# shieldplank.net
KiCad netlist of a schematic drawn in EAGLE
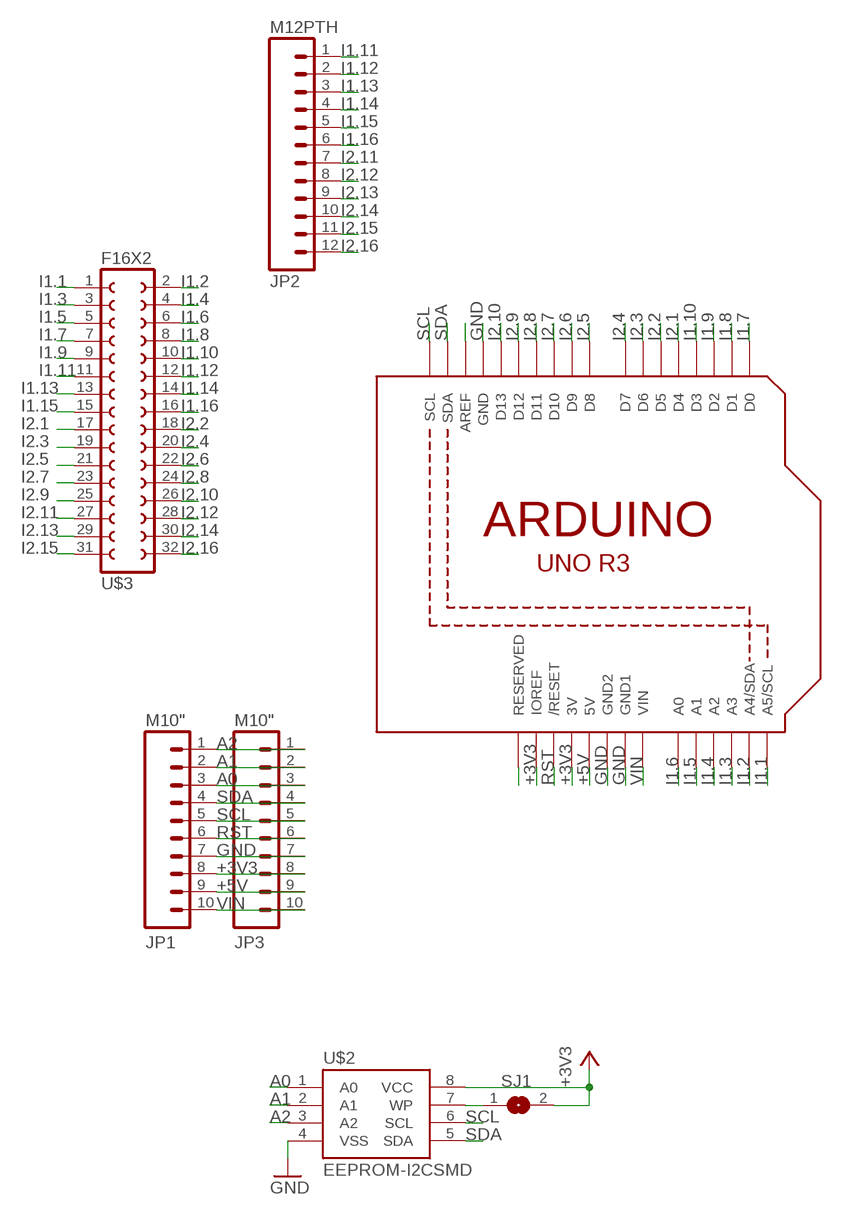
[diagram p0: schematic, sheet 1]

(export (version "E")
  (design (tool "Eeschema 10.0.6"))
  (components
    (comp (ref "JP1")
      (value "M10\"")
      (footprint "eagle-import:1X10")
      (libsource (lib "eagle-import") (part "M10{dblquote}"))
    )
    (comp (ref "JP2")
      (value "M12PTH")
      (footprint "eagle-import:1X12")
      (libsource (lib "eagle-import") (part "M12PTH"))
    )
    (comp (ref "JP3")
      (value "M10\"")
      (footprint "eagle-import:1X10")
      (libsource (lib "eagle-import") (part "M10{dblquote}"))
    )
    (comp (ref "SJ1") (value "SJ") (footprint "eagle-import:SJ") (libsource (lib "eagle-import") (part "SJ")))
    (comp (ref "U$2")
      (value "EEPROM-I2CSMD")
      (footprint "eagle-import:SO08")
      (libsource (lib "eagle-import") (part "EEPROM-I2CSMD"))
    )
    (comp (ref "U$3")
      (value "F16X2")
      (footprint "eagle-import:FE16-2")
      (libsource (lib "eagle-import") (part "F16X2"))
    )
    (comp (ref "U1")
      (value "ARDUINOR3-BPLACE")
      (footprint "eagle-import:ARDUINOR3-BPLACE")
      (libsource (lib "eagle-import") (part "ARDUINOR3-BPLACE"))
    )
  )
  (nets
    (net (code "1") (name "+3V3") (class "Default")
      (node (ref "JP1") (pin "8") (pinfunction "8_8") (pintype "passive"))
      (node (ref "JP3") (pin "8") (pinfunction "8_8") (pintype "passive"))
      (node (ref "SJ1") (pin "2") (pinfunction "2_2") (pintype "passive"))
      (node (ref "U$2") (pin "8") (pinfunction "VCC_8") (pintype "power_in"))
      (node (ref "U1") (pin "3V") (pinfunction "3V_3V") (pintype "power_in"))
      (node (ref "U1") (pin "IOREF") (pinfunction "IOREF_IOREF") (pintype "output"))
    )
    (net (code "2") (name "/+5V") (class "Default")
      (node (ref "JP1") (pin "9") (pinfunction "9_9") (pintype "passive"))
      (node (ref "JP3") (pin "9") (pinfunction "9_9") (pintype "passive"))
      (node (ref "U1") (pin "5V") (pinfunction "5V_5V") (pintype "power_in"))
    )
    (net (code "3") (name "/A0") (class "Default")
      (node (ref "JP1") (pin "3") (pinfunction "3_3") (pintype "passive"))
      (node (ref "JP3") (pin "3") (pinfunction "3_3") (pintype "passive"))
      (node (ref "U$2") (pin "1") (pinfunction "A0_1") (pintype "bidirectional"))
    )
    (net (code "4") (name "/A1") (class "Default")
      (node (ref "JP1") (pin "2") (pinfunction "2_2") (pintype "passive"))
      (node (ref "JP3") (pin "2") (pinfunction "2_2") (pintype "passive"))
      (node (ref "U$2") (pin "2") (pinfunction "A1_2") (pintype "bidirectional"))
    )
    (net (code "5") (name "/A2") (class "Default")
      (node (ref "JP1") (pin "1") (pinfunction "1_1") (pintype "passive"))
      (node (ref "JP3") (pin "1") (pinfunction "1_1") (pintype "passive"))
      (node (ref "U$2") (pin "3") (pinfunction "A2_3") (pintype "bidirectional"))
    )
    (net (code "6") (name "/I1.1") (class "Default")
      (node (ref "U$3") (pin "1") (pinfunction "1_1") (pintype "passive"))
      (node (ref "U1") (pin "A5") (pinfunction "A5/SCL_A5") (pintype "bidirectional"))
    )
    (net (code "7") (name "/I1.2") (class "Default")
      (node (ref "U$3") (pin "2") (pinfunction "2_2") (pintype "passive"))
      (node (ref "U1") (pin "A4") (pinfunction "A4/SDA_A4") (pintype "bidirectional"))
    )
    (net (code "8") (name "/I1.3") (class "Default")
      (node (ref "U$3") (pin "3") (pinfunction "3_3") (pintype "passive"))
      (node (ref "U1") (pin "A3") (pinfunction "A3_A3") (pintype "bidirectional"))
    )
    (net (code "9") (name "/I1.4") (class "Default")
      (node (ref "U$3") (pin "4") (pinfunction "4_4") (pintype "passive"))
      (node (ref "U1") (pin "A2") (pinfunction "A2_A2") (pintype "bidirectional"))
    )
    (net (code "10") (name "/I1.5") (class "Default")
      (node (ref "U$3") (pin "5") (pinfunction "5_5") (pintype "passive"))
      (node (ref "U1") (pin "A1") (pinfunction "A1_A1") (pintype "bidirectional"))
    )
    (net (code "11") (name "/I1.6") (class "Default")
      (node (ref "U$3") (pin "6") (pinfunction "6_6") (pintype "passive"))
      (node (ref "U1") (pin "A0") (pinfunction "A0_A0") (pintype "bidirectional"))
    )
    (net (code "12") (name "/I1.7") (class "Default")
      (node (ref "U$3") (pin "7") (pinfunction "7_7") (pintype "passive"))
      (node (ref "U1") (pin "D0") (pinfunction "D0_D0") (pintype "bidirectional"))
    )
    (net (code "13") (name "/I1.8") (class "Default")
      (node (ref "U$3") (pin "8") (pinfunction "8_8") (pintype "passive"))
      (node (ref "U1") (pin "D1") (pinfunction "D1_D1") (pintype "bidirectional"))
    )
    (net (code "14") (name "/I1.9") (class "Default")
      (node (ref "U$3") (pin "9") (pinfunction "9_9") (pintype "passive"))
      (node (ref "U1") (pin "D2") (pinfunction "D2_D2") (pintype "bidirectional"))
    )
    (net (code "15") (name "/I1.10") (class "Default")
      (node (ref "U$3") (pin "10") (pinfunction "10_10") (pintype "passive"))
      (node (ref "U1") (pin "D3") (pinfunction "D3_D3") (pintype "bidirectional"))
    )
    (net (code "16") (name "/I1.11") (class "Default")
      (node (ref "JP2") (pin "1") (pinfunction "1_1") (pintype "passive"))
      (node (ref "U$3") (pin "11") (pinfunction "11_11") (pintype "passive"))
    )
    (net (code "17") (name "/I1.12") (class "Default")
      (node (ref "JP2") (pin "2") (pinfunction "2_2") (pintype "passive"))
      (node (ref "U$3") (pin "12") (pinfunction "12_12") (pintype "passive"))
    )
    (net (code "18") (name "/I1.13") (class "Default")
      (node (ref "JP2") (pin "3") (pinfunction "3_3") (pintype "passive"))
      (node (ref "U$3") (pin "13") (pinfunction "13_13") (pintype "passive"))
    )
    (net (code "19") (name "/I1.14") (class "Default")
      (node (ref "JP2") (pin "4") (pinfunction "4_4") (pintype "passive"))
      (node (ref "U$3") (pin "14") (pinfunction "14_14") (pintype "passive"))
    )
    (net (code "20") (name "/I1.15") (class "Default")
      (node (ref "JP2") (pin "5") (pinfunction "5_5") (pintype "passive"))
      (node (ref "U$3") (pin "15") (pinfunction "15_15") (pintype "passive"))
    )
    (net (code "21") (name "/I1.16") (class "Default")
      (node (ref "JP2") (pin "6") (pinfunction "6_6") (pintype "passive"))
      (node (ref "U$3") (pin "16") (pinfunction "16_16") (pintype "passive"))
    )
    (net (code "22") (name "/I2.1") (class "Default")
      (node (ref "U$3") (pin "17") (pinfunction "17_17") (pintype "passive"))
      (node (ref "U1") (pin "D4") (pinfunction "D4_D4") (pintype "bidirectional"))
    )
    (net (code "23") (name "/I2.2") (class "Default")
      (node (ref "U$3") (pin "18") (pinfunction "18_18") (pintype "passive"))
      (node (ref "U1") (pin "D5") (pinfunction "D5_D5") (pintype "bidirectional"))
    )
    (net (code "24") (name "/I2.3") (class "Default")
      (node (ref "U$3") (pin "19") (pinfunction "19_19") (pintype "passive"))
      (node (ref "U1") (pin "D6") (pinfunction "D6_D6") (pintype "bidirectional"))
    )
    (net (code "25") (name "/I2.4") (class "Default")
      (node (ref "U$3") (pin "20") (pinfunction "20_20") (pintype "passive"))
      (node (ref "U1") (pin "D7") (pinfunction "D7_D7") (pintype "bidirectional"))
    )
    (net (code "26") (name "/I2.5") (class "Default")
      (node (ref "U$3") (pin "21") (pinfunction "21_21") (pintype "passive"))
      (node (ref "U1") (pin "D8") (pinfunction "D8_D8") (pintype "bidirectional"))
    )
    (net (code "27") (name "/I2.6") (class "Default")
      (node (ref "U$3") (pin "22") (pinfunction "22_22") (pintype "passive"))
      (node (ref "U1") (pin "D9") (pinfunction "D9_D9") (pintype "bidirectional"))
    )
    (net (code "28") (name "/I2.7") (class "Default")
      (node (ref "U$3") (pin "23") (pinfunction "23_23") (pintype "passive"))
      (node (ref "U1") (pin "D10") (pinfunction "D10_D10") (pintype "bidirectional"))
    )
    (net (code "29") (name "/I2.8") (class "Default")
      (node (ref "U$3") (pin "24") (pinfunction "24_24") (pintype "passive"))
      (node (ref "U1") (pin "D11") (pinfunction "D11_D11") (pintype "bidirectional"))
    )
    (net (code "30") (name "/I2.9") (class "Default")
      (node (ref "U$3") (pin "25") (pinfunction "25_25") (pintype "passive"))
      (node (ref "U1") (pin "D12") (pinfunction "D12_D12") (pintype "bidirectional"))
    )
    (net (code "31") (name "/I2.10") (class "Default")
      (node (ref "U$3") (pin "26") (pinfunction "26_26") (pintype "passive"))
      (node (ref "U1") (pin "D13") (pinfunction "D13_D13") (pintype "bidirectional"))
    )
    (net (code "32") (name "/I2.11") (class "Default")
      (node (ref "JP2") (pin "7") (pinfunction "7_7") (pintype "passive"))
      (node (ref "U$3") (pin "27") (pinfunction "27_27") (pintype "passive"))
    )
    (net (code "33") (name "/I2.12") (class "Default")
      (node (ref "JP2") (pin "8") (pinfunction "8_8") (pintype "passive"))
      (node (ref "U$3") (pin "28") (pinfunction "28_28") (pintype "passive"))
    )
    (net (code "34") (name "/I2.13") (class "Default")
      (node (ref "JP2") (pin "9") (pinfunction "9_9") (pintype "passive"))
      (node (ref "U$3") (pin "29") (pinfunction "29_29") (pintype "passive"))
    )
    (net (code "35") (name "/I2.14") (class "Default")
      (node (ref "JP2") (pin "10") (pinfunction "10_10") (pintype "passive"))
      (node (ref "U$3") (pin "30") (pinfunction "30_30") (pintype "passive"))
    )
    (net (code "36") (name "/I2.15") (class "Default")
      (node (ref "JP2") (pin "11") (pinfunction "11_11") (pintype "passive"))
      (node (ref "U$3") (pin "31") (pinfunction "31_31") (pintype "passive"))
    )
    (net (code "37") (name "/I2.16") (class "Default")
      (node (ref "JP2") (pin "12") (pinfunction "12_12") (pintype "passive"))
      (node (ref "U$3") (pin "32") (pinfunction "32_32") (pintype "passive"))
    )
    (net (code "38") (name "/RST") (class "Default")
      (node (ref "JP1") (pin "6") (pinfunction "6_6") (pintype "passive"))
      (node (ref "JP3") (pin "6") (pinfunction "6_6") (pintype "passive"))
      (node (ref "U1") (pin "RESET") (pinfunction "/RESET_RESET") (pintype "bidirectional"))
    )
    (net (code "39") (name "/SCL") (class "Default")
      (node (ref "JP1") (pin "5") (pinfunction "5_5") (pintype "passive"))
      (node (ref "JP3") (pin "5") (pinfunction "5_5") (pintype "passive"))
      (node (ref "U$2") (pin "6") (pinfunction "SCL_6") (pintype "bidirectional"))
      (node (ref "U1") (pin "SCL") (pinfunction "SCL_SCL") (pintype "bidirectional"))
    )
    (net (code "40") (name "/SDA") (class "Default")
      (node (ref "JP1") (pin "4") (pinfunction "4_4") (pintype "passive"))
      (node (ref "JP3") (pin "4") (pinfunction "4_4") (pintype "passive"))
      (node (ref "U$2") (pin "5") (pinfunction "SDA_5") (pintype "bidirectional"))
      (node (ref "U1") (pin "SDA") (pinfunction "SDA_SDA") (pintype "bidirectional"))
    )
    (net (code "41") (name "/VIN") (class "Default")
      (node (ref "JP1") (pin "10") (pinfunction "10_10") (pintype "passive"))
      (node (ref "JP3") (pin "10") (pinfunction "10_10") (pintype "passive"))
      (node (ref "U1") (pin "VIN") (pinfunction "VIN_VIN") (pintype "power_in"))
    )
    (net (code "42") (name "GND") (class "Default")
      (node (ref "JP1") (pin "7") (pinfunction "7_7") (pintype "passive"))
      (node (ref "JP3") (pin "7") (pinfunction "7_7") (pintype "passive"))
      (node (ref "U$2") (pin "4") (pinfunction "VSS_4") (pintype "power_in"))
      (node (ref "U1") (pin "GND") (pinfunction "GND_GND") (pintype "power_in"))
      (node (ref "U1") (pin "GND1") (pinfunction "GND1_GND1") (pintype "power_in"))
      (node (ref "U1") (pin "GND2") (pinfunction "GND2_GND2") (pintype "power_in"))
    )
    (net (code "43") (name "Net-(U$2-WP)") (class "Default")
      (node (ref "SJ1") (pin "1") (pinfunction "1_1") (pintype "passive"))
      (node (ref "U$2") (pin "7") (pinfunction "WP_7") (pintype "bidirectional"))
    )
    (net (code "44") (name "unconnected-(U1-PadAREF)") (class "Default")
      (node (ref "U1") (pin "AREF") (pinfunction "AREF_AREF") (pintype "bidirectional"))
    )
    (net (code "45") (name "unconnected-(U1-PadRESERVED)") (class "Default")
      (node (ref "U1") (pin "RESERVED") (pinfunction "RESERVED_RESERVED") (pintype "no_connect"))
    )
  )
)
